# T41.net
KiCad netlist of a schematic drawn in EAGLE
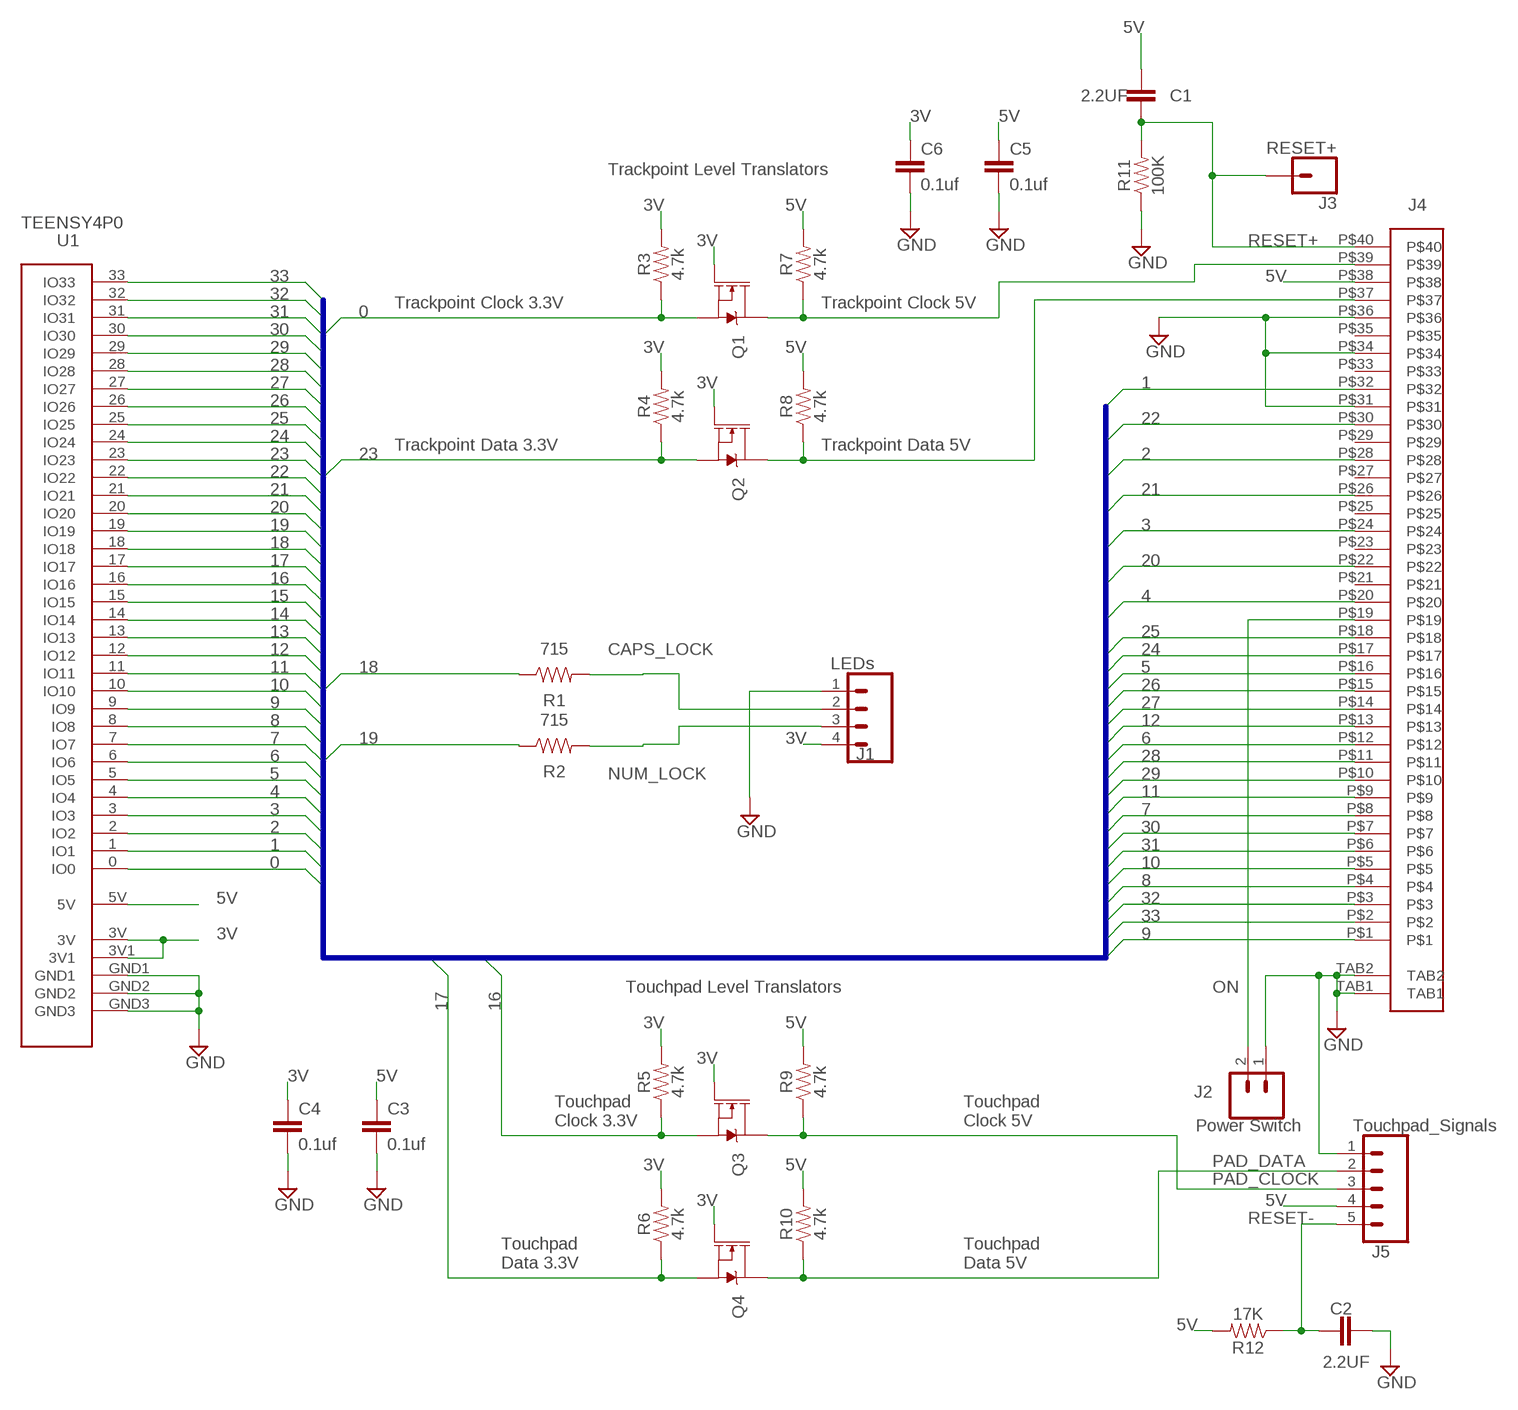
[diagram p0: schematic, sheet 1]

(export (version "E")
  (design (tool "Eeschema 10.0.6"))
  (components
    (comp (ref "C1")
      (value "2.2UF")
      (footprint "eagle-import:0603_CAP")
      (libsource (lib "eagle-import") (part "0603_CAP"))
    )
    (comp (ref "C2")
      (value "2.2UF")
      (footprint "eagle-import:0603_CAP")
      (libsource (lib "eagle-import") (part "0603_CAP"))
    )
    (comp (ref "C3")
      (value "0.1uf")
      (footprint "eagle-import:0603_CAP")
      (libsource (lib "eagle-import") (part "0603_CAP"))
    )
    (comp (ref "C4")
      (value "0.1uf")
      (footprint "eagle-import:0603_CAP")
      (libsource (lib "eagle-import") (part "0603_CAP"))
    )
    (comp (ref "C5")
      (value "0.1uf")
      (footprint "eagle-import:0603_CAP")
      (libsource (lib "eagle-import") (part "0603_CAP"))
    )
    (comp (ref "C6")
      (value "0.1uf")
      (footprint "eagle-import:0603_CAP")
      (libsource (lib "eagle-import") (part "0603_CAP"))
    )
    (comp (ref "J1")
      (value "LEDs")
      (footprint "eagle-import:1X04")
      (libsource (lib "eagle-import") (part "CONN_04"))
    )
    (comp (ref "J2")
      (value "Power Switch")
      (footprint "eagle-import:1X02")
      (libsource (lib "eagle-import") (part "CONN_02"))
    )
    (comp (ref "J3")
      (value "RESET+")
      (footprint "eagle-import:1X01_NO_SILK")
      (libsource (lib "eagle-import") (part "CONN_01PTH_NO_SILK_YES_STOP"))
    )
    (comp (ref "J4")
      (value "KX14-40K5DE")
      (footprint "eagle-import:KX14_40K5DE")
      (libsource (lib "eagle-import") (part "KX14_40K5DE"))
    )
    (comp (ref "J5")
      (value "Touchpad_Signals")
      (footprint "eagle-import:1X05")
      (libsource (lib "eagle-import") (part "CONN_05"))
    )
    (comp (ref "Q1")
      (value "220mA/50V/3.5Ω")
      (footprint "eagle-import:SOT23-3")
      (libsource (lib "eagle-import") (part "MOSFET-NCH-BSS138"))
    )
    (comp (ref "Q2")
      (value "220mA/50V/3.5Ω")
      (footprint "eagle-import:SOT23-3")
      (libsource (lib "eagle-import") (part "MOSFET-NCH-BSS138"))
    )
    (comp (ref "Q3")
      (value "220mA/50V/3.5Ω")
      (footprint "eagle-import:SOT23-3")
      (libsource (lib "eagle-import") (part "MOSFET-NCH-BSS138"))
    )
    (comp (ref "Q4")
      (value "220mA/50V/3.5Ω")
      (footprint "eagle-import:SOT23-3")
      (libsource (lib "eagle-import") (part "MOSFET-NCH-BSS138"))
    )
    (comp (ref "R1")
      (value "715")
      (footprint "eagle-import:0603")
      (libsource (lib "eagle-import") (part "715OHM-0603-1/10W-1%"))
    )
    (comp (ref "R2")
      (value "715")
      (footprint "eagle-import:0603")
      (libsource (lib "eagle-import") (part "715OHM-0603-1/10W-1%"))
    )
    (comp (ref "R3")
      (value "4.7k")
      (footprint "eagle-import:0603")
      (libsource (lib "eagle-import") (part "4.7KOHM-0603-1/10W-1%"))
    )
    (comp (ref "R4")
      (value "4.7k")
      (footprint "eagle-import:0603")
      (libsource (lib "eagle-import") (part "4.7KOHM-0603-1/10W-1%"))
    )
    (comp (ref "R5")
      (value "4.7k")
      (footprint "eagle-import:0603")
      (libsource (lib "eagle-import") (part "4.7KOHM-0603-1/10W-1%"))
    )
    (comp (ref "R6")
      (value "4.7k")
      (footprint "eagle-import:0603")
      (libsource (lib "eagle-import") (part "4.7KOHM-0603-1/10W-1%"))
    )
    (comp (ref "R7")
      (value "4.7k")
      (footprint "eagle-import:0603")
      (libsource (lib "eagle-import") (part "4.7KOHM-0603-1/10W-1%"))
    )
    (comp (ref "R8")
      (value "4.7k")
      (footprint "eagle-import:0603")
      (libsource (lib "eagle-import") (part "4.7KOHM-0603-1/10W-1%"))
    )
    (comp (ref "R9")
      (value "4.7k")
      (footprint "eagle-import:0603")
      (libsource (lib "eagle-import") (part "4.7KOHM-0603-1/10W-1%"))
    )
    (comp (ref "R10")
      (value "4.7k")
      (footprint "eagle-import:0603")
      (libsource (lib "eagle-import") (part "4.7KOHM-0603-1/10W-1%"))
    )
    (comp (ref "R11")
      (value "100K")
      (footprint "eagle-import:0603_RESISTOR")
      (libsource (lib "eagle-import") (part "0603_RESISTOR"))
    )
    (comp (ref "R12")
      (value "17K")
      (footprint "eagle-import:0603_RESISTOR")
      (libsource (lib "eagle-import") (part "0603_RESISTOR"))
    )
    (comp (ref "U1")
      (value "TEENSY4P0")
      (footprint "eagle-import:TEENSY4P0")
      (libsource (lib "eagle-import") (part "TEENSY4P0"))
    )
  )
  (nets
    (net (code "1") (name "/0") (class "Default")
      (node (ref "Q1") (pin "2") (pinfunction "S_2") (pintype "bidirectional"))
      (node (ref "R3") (pin "1") (pinfunction "1_1") (pintype "passive"))
      (node (ref "U1") (pin "0") (pinfunction "IO0_0") (pintype "bidirectional"))
    )
    (net (code "2") (name "/1") (class "Default")
      (node (ref "J4") (pin "P$32") (pinfunction "P$32_P$32") (pintype "bidirectional"))
      (node (ref "U1") (pin "1") (pinfunction "IO1_1") (pintype "bidirectional"))
    )
    (net (code "3") (name "/2") (class "Default")
      (node (ref "J4") (pin "P$28") (pinfunction "P$28_P$28") (pintype "bidirectional"))
      (node (ref "U1") (pin "2") (pinfunction "IO2_2") (pintype "bidirectional"))
    )
    (net (code "4") (name "/3") (class "Default")
      (node (ref "J4") (pin "P$24") (pinfunction "P$24_P$24") (pintype "bidirectional"))
      (node (ref "U1") (pin "3") (pinfunction "IO3_3") (pintype "bidirectional"))
    )
    (net (code "5") (name "/3V") (class "Default")
      (node (ref "C4") (pin "1") (pinfunction "1_1") (pintype "passive"))
      (node (ref "C6") (pin "1") (pinfunction "1_1") (pintype "passive"))
      (node (ref "J1") (pin "4") (pinfunction "4_4") (pintype "passive"))
      (node (ref "Q1") (pin "1") (pinfunction "G_1") (pintype "bidirectional"))
      (node (ref "Q2") (pin "1") (pinfunction "G_1") (pintype "bidirectional"))
      (node (ref "Q3") (pin "1") (pinfunction "G_1") (pintype "bidirectional"))
      (node (ref "Q4") (pin "1") (pinfunction "G_1") (pintype "bidirectional"))
      (node (ref "R3") (pin "2") (pinfunction "2_2") (pintype "passive"))
      (node (ref "R4") (pin "2") (pinfunction "2_2") (pintype "passive"))
      (node (ref "R5") (pin "2") (pinfunction "2_2") (pintype "passive"))
      (node (ref "R6") (pin "2") (pinfunction "2_2") (pintype "passive"))
      (node (ref "U1") (pin "3V") (pinfunction "3V_3V") (pintype "bidirectional"))
      (node (ref "U1") (pin "3V1") (pinfunction "3V1_3V1") (pintype "bidirectional"))
    )
    (net (code "6") (name "/4") (class "Default")
      (node (ref "J4") (pin "P$20") (pinfunction "P$20_P$20") (pintype "bidirectional"))
      (node (ref "U1") (pin "4") (pinfunction "IO4_4") (pintype "bidirectional"))
    )
    (net (code "7") (name "/5") (class "Default")
      (node (ref "J4") (pin "P$16") (pinfunction "P$16_P$16") (pintype "bidirectional"))
      (node (ref "U1") (pin "5") (pinfunction "IO5_5") (pintype "bidirectional"))
    )
    (net (code "8") (name "/5V") (class "Default")
      (node (ref "C1") (pin "1") (pinfunction "1_1") (pintype "passive"))
      (node (ref "C3") (pin "1") (pinfunction "1_1") (pintype "passive"))
      (node (ref "C5") (pin "1") (pinfunction "1_1") (pintype "passive"))
      (node (ref "J4") (pin "P$38") (pinfunction "P$38_P$38") (pintype "bidirectional"))
      (node (ref "J5") (pin "4") (pinfunction "4_4") (pintype "passive"))
      (node (ref "R10") (pin "2") (pinfunction "2_2") (pintype "passive"))
      (node (ref "R12") (pin "2") (pinfunction "2_2") (pintype "passive"))
      (node (ref "R7") (pin "2") (pinfunction "2_2") (pintype "passive"))
      (node (ref "R8") (pin "2") (pinfunction "2_2") (pintype "passive"))
      (node (ref "R9") (pin "2") (pinfunction "2_2") (pintype "passive"))
      (node (ref "U1") (pin "5V") (pinfunction "5V_5V") (pintype "bidirectional"))
    )
    (net (code "9") (name "/6") (class "Default")
      (node (ref "J4") (pin "P$12") (pinfunction "P$12_P$12") (pintype "bidirectional"))
      (node (ref "U1") (pin "6") (pinfunction "IO6_6") (pintype "bidirectional"))
    )
    (net (code "10") (name "/7") (class "Default")
      (node (ref "J4") (pin "P$8") (pinfunction "P$8_P$8") (pintype "bidirectional"))
      (node (ref "U1") (pin "7") (pinfunction "IO7_7") (pintype "bidirectional"))
    )
    (net (code "11") (name "/8") (class "Default")
      (node (ref "J4") (pin "P$4") (pinfunction "P$4_P$4") (pintype "bidirectional"))
      (node (ref "U1") (pin "8") (pinfunction "IO8_8") (pintype "bidirectional"))
    )
    (net (code "12") (name "/9") (class "Default")
      (node (ref "J4") (pin "P$1") (pinfunction "P$1_P$1") (pintype "bidirectional"))
      (node (ref "U1") (pin "9") (pinfunction "IO9_9") (pintype "bidirectional"))
    )
    (net (code "13") (name "/10") (class "Default")
      (node (ref "J4") (pin "P$5") (pinfunction "P$5_P$5") (pintype "bidirectional"))
      (node (ref "U1") (pin "10") (pinfunction "IO10_10") (pintype "bidirectional"))
    )
    (net (code "14") (name "/11") (class "Default")
      (node (ref "J4") (pin "P$9") (pinfunction "P$9_P$9") (pintype "bidirectional"))
      (node (ref "U1") (pin "11") (pinfunction "IO11_11") (pintype "bidirectional"))
    )
    (net (code "15") (name "/12") (class "Default")
      (node (ref "J4") (pin "P$13") (pinfunction "P$13_P$13") (pintype "bidirectional"))
      (node (ref "U1") (pin "12") (pinfunction "IO12_12") (pintype "bidirectional"))
    )
    (net (code "16") (name "/13") (class "Default")
      (node (ref "U1") (pin "13") (pinfunction "IO13_13") (pintype "bidirectional"))
    )
    (net (code "17") (name "/14") (class "Default")
      (node (ref "U1") (pin "14") (pinfunction "IO14_14") (pintype "bidirectional"))
    )
    (net (code "18") (name "/15") (class "Default")
      (node (ref "U1") (pin "15") (pinfunction "IO15_15") (pintype "bidirectional"))
    )
    (net (code "19") (name "/16") (class "Default")
      (node (ref "Q3") (pin "2") (pinfunction "S_2") (pintype "bidirectional"))
      (node (ref "R5") (pin "1") (pinfunction "1_1") (pintype "passive"))
      (node (ref "U1") (pin "16") (pinfunction "IO16_16") (pintype "bidirectional"))
    )
    (net (code "20") (name "/17") (class "Default")
      (node (ref "Q4") (pin "2") (pinfunction "S_2") (pintype "bidirectional"))
      (node (ref "R6") (pin "1") (pinfunction "1_1") (pintype "passive"))
      (node (ref "U1") (pin "17") (pinfunction "IO17_17") (pintype "bidirectional"))
    )
    (net (code "21") (name "/18") (class "Default")
      (node (ref "R1") (pin "1") (pinfunction "1_1") (pintype "passive"))
      (node (ref "U1") (pin "18") (pinfunction "IO18_18") (pintype "bidirectional"))
    )
    (net (code "22") (name "/19") (class "Default")
      (node (ref "R2") (pin "1") (pinfunction "1_1") (pintype "passive"))
      (node (ref "U1") (pin "19") (pinfunction "IO19_19") (pintype "bidirectional"))
    )
    (net (code "23") (name "/20") (class "Default")
      (node (ref "J4") (pin "P$22") (pinfunction "P$22_P$22") (pintype "bidirectional"))
      (node (ref "U1") (pin "20") (pinfunction "IO20_20") (pintype "bidirectional"))
    )
    (net (code "24") (name "/21") (class "Default")
      (node (ref "J4") (pin "P$26") (pinfunction "P$26_P$26") (pintype "bidirectional"))
      (node (ref "U1") (pin "21") (pinfunction "IO21_21") (pintype "bidirectional"))
    )
    (net (code "25") (name "/22") (class "Default")
      (node (ref "J4") (pin "P$30") (pinfunction "P$30_P$30") (pintype "bidirectional"))
      (node (ref "U1") (pin "22") (pinfunction "IO22_22") (pintype "bidirectional"))
    )
    (net (code "26") (name "/23") (class "Default")
      (node (ref "Q2") (pin "2") (pinfunction "S_2") (pintype "bidirectional"))
      (node (ref "R4") (pin "1") (pinfunction "1_1") (pintype "passive"))
      (node (ref "U1") (pin "23") (pinfunction "IO23_23") (pintype "bidirectional"))
    )
    (net (code "27") (name "/24") (class "Default")
      (node (ref "J4") (pin "P$17") (pinfunction "P$17_P$17") (pintype "bidirectional"))
      (node (ref "U1") (pin "24") (pinfunction "IO24_24") (pintype "bidirectional"))
    )
    (net (code "28") (name "/25") (class "Default")
      (node (ref "J4") (pin "P$18") (pinfunction "P$18_P$18") (pintype "bidirectional"))
      (node (ref "U1") (pin "25") (pinfunction "IO25_25") (pintype "bidirectional"))
    )
    (net (code "29") (name "/26") (class "Default")
      (node (ref "J4") (pin "P$15") (pinfunction "P$15_P$15") (pintype "bidirectional"))
      (node (ref "U1") (pin "26") (pinfunction "IO26_26") (pintype "bidirectional"))
    )
    (net (code "30") (name "/27") (class "Default")
      (node (ref "J4") (pin "P$14") (pinfunction "P$14_P$14") (pintype "bidirectional"))
      (node (ref "U1") (pin "27") (pinfunction "IO27_27") (pintype "bidirectional"))
    )
    (net (code "31") (name "/28") (class "Default")
      (node (ref "J4") (pin "P$11") (pinfunction "P$11_P$11") (pintype "bidirectional"))
      (node (ref "U1") (pin "28") (pinfunction "IO28_28") (pintype "bidirectional"))
    )
    (net (code "32") (name "/29") (class "Default")
      (node (ref "J4") (pin "P$10") (pinfunction "P$10_P$10") (pintype "bidirectional"))
      (node (ref "U1") (pin "29") (pinfunction "IO29_29") (pintype "bidirectional"))
    )
    (net (code "33") (name "/30") (class "Default")
      (node (ref "J4") (pin "P$7") (pinfunction "P$7_P$7") (pintype "bidirectional"))
      (node (ref "U1") (pin "30") (pinfunction "IO30_30") (pintype "bidirectional"))
    )
    (net (code "34") (name "/31") (class "Default")
      (node (ref "J4") (pin "P$6") (pinfunction "P$6_P$6") (pintype "bidirectional"))
      (node (ref "U1") (pin "31") (pinfunction "IO31_31") (pintype "bidirectional"))
    )
    (net (code "35") (name "/32") (class "Default")
      (node (ref "J4") (pin "P$3") (pinfunction "P$3_P$3") (pintype "bidirectional"))
      (node (ref "U1") (pin "32") (pinfunction "IO32_32") (pintype "bidirectional"))
    )
    (net (code "36") (name "/33") (class "Default")
      (node (ref "J4") (pin "P$2") (pinfunction "P$2_P$2") (pintype "bidirectional"))
      (node (ref "U1") (pin "33") (pinfunction "IO33_33") (pintype "bidirectional"))
    )
    (net (code "37") (name "/CAPS_LOCK") (class "Default")
      (node (ref "J1") (pin "2") (pinfunction "2_2") (pintype "passive"))
      (node (ref "R1") (pin "2") (pinfunction "2_2") (pintype "passive"))
    )
    (net (code "38") (name "/NUM_LOCK") (class "Default")
      (node (ref "J1") (pin "3") (pinfunction "3_3") (pintype "passive"))
      (node (ref "R2") (pin "2") (pinfunction "2_2") (pintype "passive"))
    )
    (net (code "39") (name "/ON") (class "Default")
      (node (ref "J2") (pin "2") (pinfunction "2_2") (pintype "passive"))
      (node (ref "J4") (pin "P$19") (pinfunction "P$19_P$19") (pintype "bidirectional"))
    )
    (net (code "40") (name "/PAD_CLOCK") (class "Default")
      (node (ref "J5") (pin "3") (pinfunction "3_3") (pintype "passive"))
      (node (ref "Q3") (pin "3") (pinfunction "D_3") (pintype "bidirectional"))
      (node (ref "R9") (pin "1") (pinfunction "1_1") (pintype "passive"))
    )
    (net (code "41") (name "/PAD_DATA") (class "Default")
      (node (ref "J5") (pin "2") (pinfunction "2_2") (pintype "passive"))
      (node (ref "Q4") (pin "3") (pinfunction "D_3") (pintype "bidirectional"))
      (node (ref "R10") (pin "1") (pinfunction "1_1") (pintype "passive"))
    )
    (net (code "42") (name "/RESET+") (class "Default")
      (node (ref "C1") (pin "2") (pinfunction "2_2") (pintype "passive"))
      (node (ref "J3") (pin "1") (pinfunction "1_1") (pintype "passive"))
      (node (ref "J4") (pin "P$40") (pinfunction "P$40_P$40") (pintype "bidirectional"))
      (node (ref "R11") (pin "2") (pinfunction "2_2") (pintype "passive"))
    )
    (net (code "43") (name "/RESET-") (class "Default")
      (node (ref "C2") (pin "1") (pinfunction "1_1") (pintype "passive"))
      (node (ref "J5") (pin "5") (pinfunction "5_5") (pintype "passive"))
      (node (ref "R12") (pin "1") (pinfunction "1_1") (pintype "passive"))
    )
    (net (code "44") (name "GND") (class "Default")
      (node (ref "C2") (pin "2") (pinfunction "2_2") (pintype "passive"))
      (node (ref "C3") (pin "2") (pinfunction "2_2") (pintype "passive"))
      (node (ref "C4") (pin "2") (pinfunction "2_2") (pintype "passive"))
      (node (ref "C5") (pin "2") (pinfunction "2_2") (pintype "passive"))
      (node (ref "C6") (pin "2") (pinfunction "2_2") (pintype "passive"))
      (node (ref "J1") (pin "1") (pinfunction "1_1") (pintype "passive"))
      (node (ref "J2") (pin "1") (pinfunction "1_1") (pintype "passive"))
      (node (ref "J4") (pin "P$31") (pinfunction "P$31_P$31") (pintype "bidirectional"))
      (node (ref "J4") (pin "P$34") (pinfunction "P$34_P$34") (pintype "bidirectional"))
      (node (ref "J4") (pin "P$36") (pinfunction "P$36_P$36") (pintype "bidirectional"))
      (node (ref "J4") (pin "TAB1") (pinfunction "TAB1_TAB1") (pintype "bidirectional"))
      (node (ref "J4") (pin "TAB2") (pinfunction "TAB2_TAB2") (pintype "bidirectional"))
      (node (ref "J5") (pin "1") (pinfunction "1_1") (pintype "passive"))
      (node (ref "R11") (pin "1") (pinfunction "1_1") (pintype "passive"))
      (node (ref "U1") (pin "GND1") (pinfunction "GND1_GND1") (pintype "bidirectional"))
      (node (ref "U1") (pin "GND2") (pinfunction "GND2_GND2") (pintype "bidirectional"))
      (node (ref "U1") (pin "GND3") (pinfunction "GND3_GND3") (pintype "bidirectional"))
    )
    (net (code "45") (name "Net-(Q1-D)") (class "Default")
      (node (ref "J4") (pin "P$39") (pinfunction "P$39_P$39") (pintype "bidirectional"))
      (node (ref "Q1") (pin "3") (pinfunction "D_3") (pintype "bidirectional"))
      (node (ref "R7") (pin "1") (pinfunction "1_1") (pintype "passive"))
    )
    (net (code "46") (name "Net-(Q2-D)") (class "Default")
      (node (ref "J4") (pin "P$37") (pinfunction "P$37_P$37") (pintype "bidirectional"))
      (node (ref "Q2") (pin "3") (pinfunction "D_3") (pintype "bidirectional"))
      (node (ref "R8") (pin "1") (pinfunction "1_1") (pintype "passive"))
    )
    (net (code "47") (name "unconnected-(J4-PadP$21)") (class "Default")
      (node (ref "J4") (pin "P$21") (pinfunction "P$21_P$21") (pintype "bidirectional"))
    )
    (net (code "48") (name "unconnected-(J4-PadP$23)") (class "Default")
      (node (ref "J4") (pin "P$23") (pinfunction "P$23_P$23") (pintype "bidirectional"))
    )
    (net (code "49") (name "unconnected-(J4-PadP$25)") (class "Default")
      (node (ref "J4") (pin "P$25") (pinfunction "P$25_P$25") (pintype "bidirectional"))
    )
    (net (code "50") (name "unconnected-(J4-PadP$27)") (class "Default")
      (node (ref "J4") (pin "P$27") (pinfunction "P$27_P$27") (pintype "bidirectional"))
    )
    (net (code "51") (name "unconnected-(J4-PadP$29)") (class "Default")
      (node (ref "J4") (pin "P$29") (pinfunction "P$29_P$29") (pintype "bidirectional"))
    )
    (net (code "52") (name "unconnected-(J4-PadP$33)") (class "Default")
      (node (ref "J4") (pin "P$33") (pinfunction "P$33_P$33") (pintype "bidirectional"))
    )
    (net (code "53") (name "unconnected-(J4-PadP$35)") (class "Default")
      (node (ref "J4") (pin "P$35") (pinfunction "P$35_P$35") (pintype "bidirectional"))
    )
  )
)
